# owl-digital-2.net
KiCad netlist of a schematic drawn in EAGLE
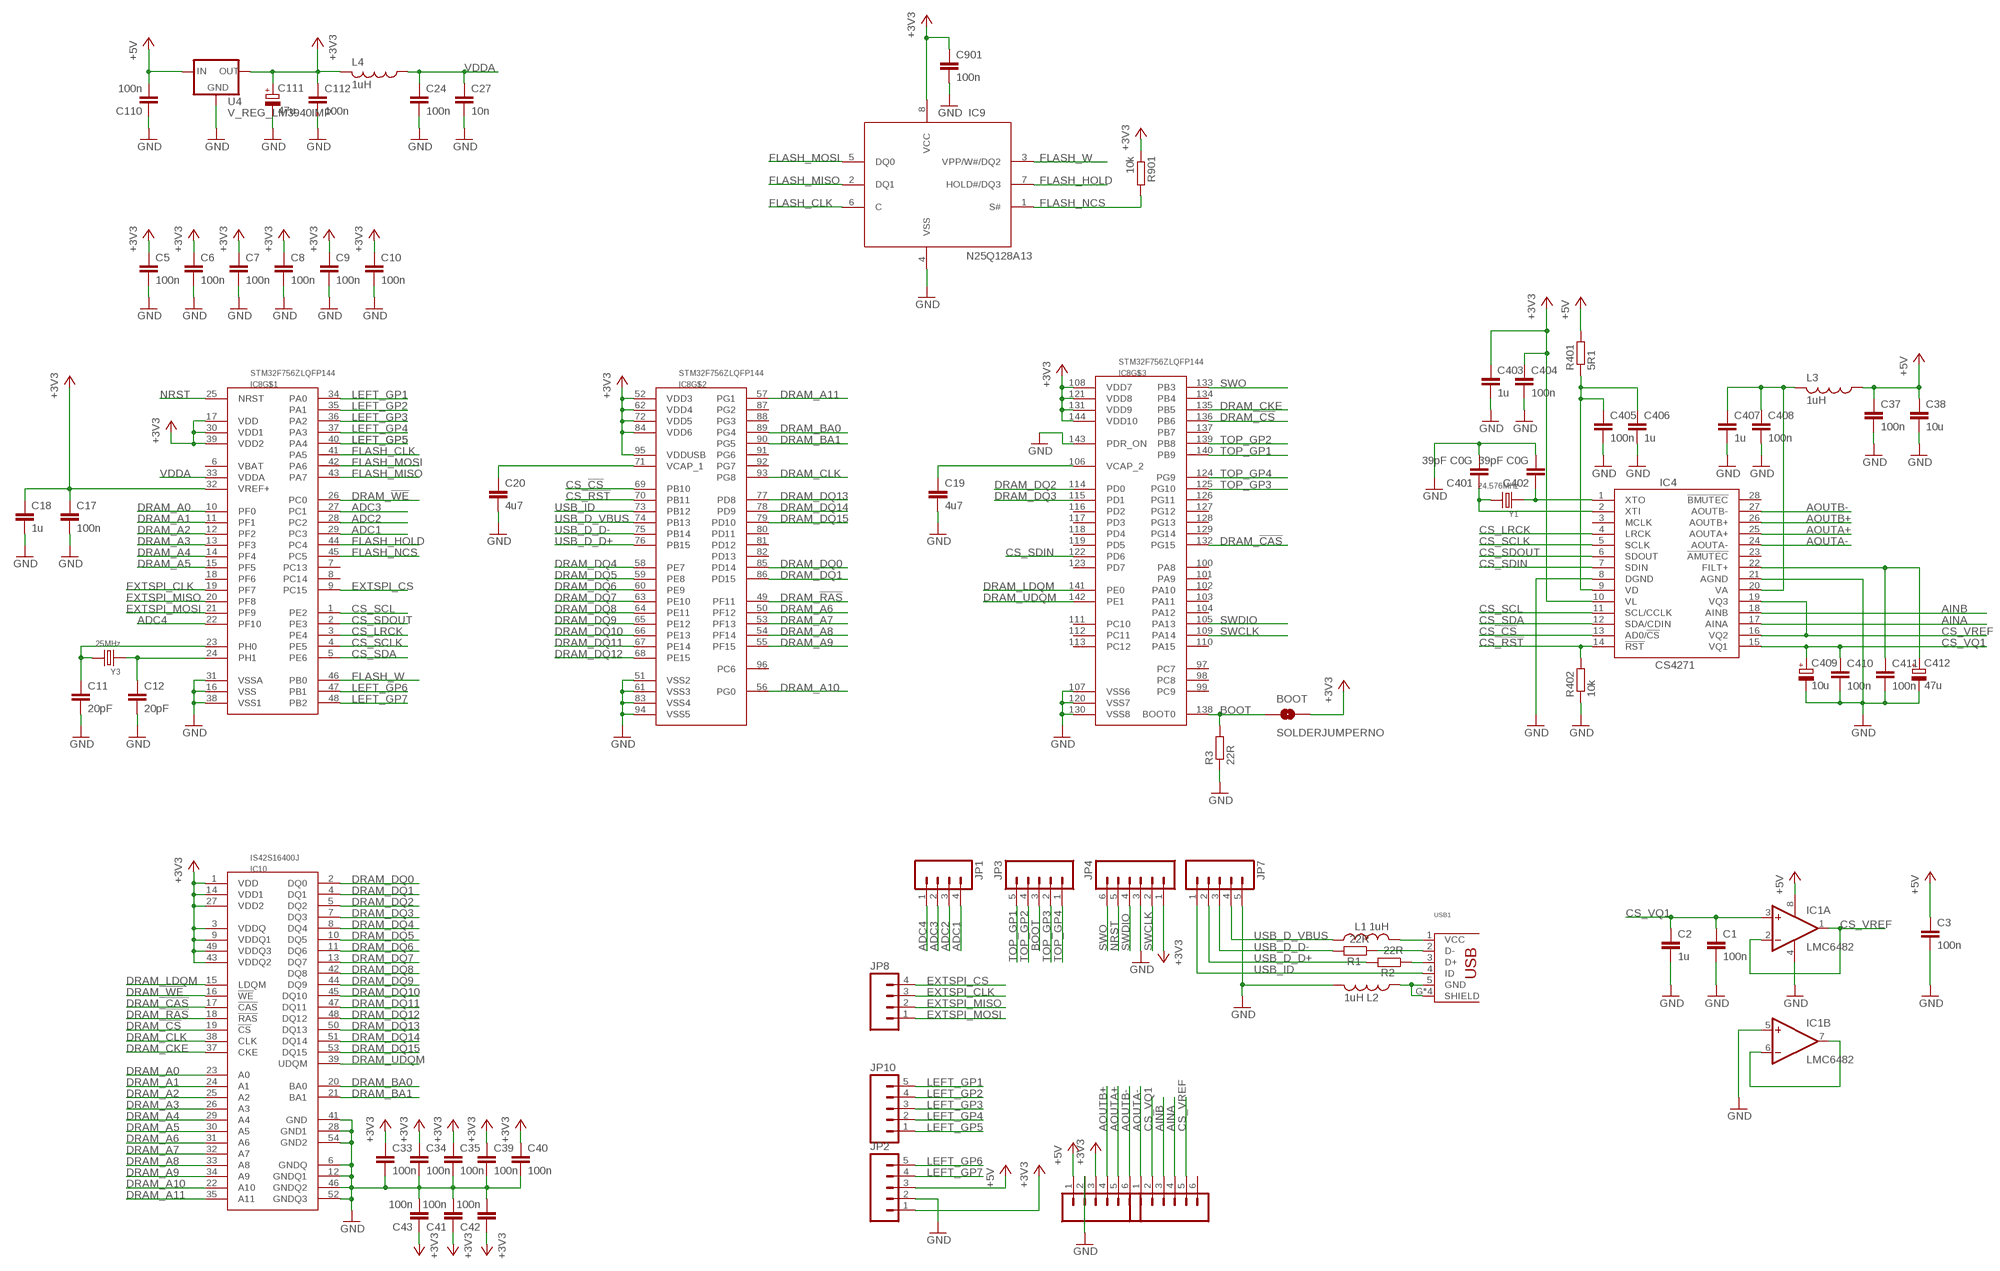
[diagram p0: schematic, sheet 1]

(export (version "E")
  (design (tool "Eeschema 10.0.6"))
  (components
    (comp (ref "BOOT")
      (value "SOLDERJUMPERNO")
      (footprint "eagle-import:SJ_2S-NO")
      (libsource (lib "eagle-import") (part "SOLDERJUMPERNO"))
    )
    (comp (ref "C1")
      (value "100n")
      (footprint "eagle-import:C0603")
      (libsource (lib "eagle-import") (part "C-EUC0603"))
    )
    (comp (ref "C2")
      (value "1u")
      (footprint "eagle-import:C0603")
      (libsource (lib "eagle-import") (part "C-EUC0603"))
    )
    (comp (ref "C3")
      (value "100n")
      (footprint "eagle-import:C0603")
      (libsource (lib "eagle-import") (part "C-EUC0603"))
    )
    (comp (ref "C5")
      (value "100n")
      (footprint "eagle-import:C0603")
      (libsource (lib "eagle-import") (part "C-EUC0603"))
    )
    (comp (ref "C6")
      (value "100n")
      (footprint "eagle-import:C0603")
      (libsource (lib "eagle-import") (part "C-EUC0603"))
    )
    (comp (ref "C7")
      (value "100n")
      (footprint "eagle-import:C0603")
      (libsource (lib "eagle-import") (part "C-EUC0603"))
    )
    (comp (ref "C8")
      (value "100n")
      (footprint "eagle-import:C0603")
      (libsource (lib "eagle-import") (part "C-EUC0603"))
    )
    (comp (ref "C9")
      (value "100n")
      (footprint "eagle-import:C0603")
      (libsource (lib "eagle-import") (part "C-EUC0603"))
    )
    (comp (ref "C10")
      (value "100n")
      (footprint "eagle-import:C0603")
      (libsource (lib "eagle-import") (part "C-EUC0603"))
    )
    (comp (ref "C11")
      (value "20pF")
      (footprint "eagle-import:C0603")
      (libsource (lib "eagle-import") (part "C-EUC0603"))
    )
    (comp (ref "C12")
      (value "20pF")
      (footprint "eagle-import:C0603")
      (libsource (lib "eagle-import") (part "C-EUC0603"))
    )
    (comp (ref "C17")
      (value "100n")
      (footprint "eagle-import:C0603")
      (libsource (lib "eagle-import") (part "C-EUC0603"))
    )
    (comp (ref "C18")
      (value "1u")
      (footprint "eagle-import:C0603")
      (libsource (lib "eagle-import") (part "C-EUC0603"))
    )
    (comp (ref "C19")
      (value "4u7")
      (footprint "eagle-import:C0603")
      (libsource (lib "eagle-import") (part "C-EUC0603"))
    )
    (comp (ref "C20")
      (value "4u7")
      (footprint "eagle-import:C0603")
      (libsource (lib "eagle-import") (part "C-EUC0603"))
    )
    (comp (ref "C24")
      (value "100n")
      (footprint "eagle-import:C0603")
      (libsource (lib "eagle-import") (part "C-EUC0603"))
    )
    (comp (ref "C27")
      (value "10n")
      (footprint "eagle-import:C0603")
      (libsource (lib "eagle-import") (part "C-EUC0603"))
    )
    (comp (ref "C33")
      (value "100n")
      (footprint "eagle-import:C0603")
      (libsource (lib "eagle-import") (part "C-EUC0603"))
    )
    (comp (ref "C34")
      (value "100n")
      (footprint "eagle-import:C0603")
      (libsource (lib "eagle-import") (part "C-EUC0603"))
    )
    (comp (ref "C35")
      (value "100n")
      (footprint "eagle-import:C0603")
      (libsource (lib "eagle-import") (part "C-EUC0603"))
    )
    (comp (ref "C37")
      (value "100n")
      (footprint "eagle-import:C0603")
      (libsource (lib "eagle-import") (part "C-EUC0603"))
    )
    (comp (ref "C38")
      (value "10u")
      (footprint "eagle-import:C1206")
      (libsource (lib "eagle-import") (part "C-EUC1206"))
    )
    (comp (ref "C39")
      (value "100n")
      (footprint "eagle-import:C0603")
      (libsource (lib "eagle-import") (part "C-EUC0603"))
    )
    (comp (ref "C40")
      (value "100n")
      (footprint "eagle-import:C0603")
      (libsource (lib "eagle-import") (part "C-EUC0603"))
    )
    (comp (ref "C41")
      (value "100n")
      (footprint "eagle-import:C0603")
      (libsource (lib "eagle-import") (part "C-EUC0603"))
    )
    (comp (ref "C42")
      (value "100n")
      (footprint "eagle-import:C0603")
      (libsource (lib "eagle-import") (part "C-EUC0603"))
    )
    (comp (ref "C43")
      (value "100n")
      (footprint "eagle-import:C0603")
      (libsource (lib "eagle-import") (part "C-EUC0603"))
    )
    (comp (ref "C110")
      (value "100n")
      (footprint "eagle-import:C0603")
      (libsource (lib "eagle-import") (part "C-EUC0603"))
    )
    (comp (ref "C111")
      (value "47u")
      (footprint "eagle-import:CPOL-5")
      (libsource (lib "eagle-import") (part "CPOL-EU153CLV-0505"))
    )
    (comp (ref "C112")
      (value "100n")
      (footprint "eagle-import:C0603")
      (libsource (lib "eagle-import") (part "C-EUC0603"))
    )
    (comp (ref "C401")
      (value "39pF C0G")
      (footprint "eagle-import:C0603")
      (libsource (lib "eagle-import") (part "C-EUC0603"))
    )
    (comp (ref "C402")
      (value "39pF C0G")
      (footprint "eagle-import:C0603")
      (libsource (lib "eagle-import") (part "C-EUC0603"))
    )
    (comp (ref "C403")
      (value "1u")
      (footprint "eagle-import:C0603")
      (libsource (lib "eagle-import") (part "C-EUC0603"))
    )
    (comp (ref "C404")
      (value "100n")
      (footprint "eagle-import:C0603")
      (libsource (lib "eagle-import") (part "C-EUC0603"))
    )
    (comp (ref "C405")
      (value "100n")
      (footprint "eagle-import:C0603")
      (libsource (lib "eagle-import") (part "C-EUC0603"))
    )
    (comp (ref "C406")
      (value "1u")
      (footprint "eagle-import:C0603")
      (libsource (lib "eagle-import") (part "C-EUC0603"))
    )
    (comp (ref "C407")
      (value "1u")
      (footprint "eagle-import:C0603")
      (libsource (lib "eagle-import") (part "C-EUC0603"))
    )
    (comp (ref "C408")
      (value "100n")
      (footprint "eagle-import:C0603")
      (libsource (lib "eagle-import") (part "C-EUC0603"))
    )
    (comp (ref "C409")
      (value "10u")
      (footprint "eagle-import:CPOL-5")
      (libsource (lib "eagle-import") (part "CPOL-EU153CLV-0505"))
    )
    (comp (ref "C410")
      (value "100n")
      (footprint "eagle-import:C0603")
      (libsource (lib "eagle-import") (part "C-EUC0603"))
    )
    (comp (ref "C411")
      (value "100n")
      (footprint "eagle-import:C0603")
      (libsource (lib "eagle-import") (part "C-EUC0603"))
    )
    (comp (ref "C412")
      (value "47u")
      (footprint "eagle-import:CPOL-5")
      (libsource (lib "eagle-import") (part "CPOL-EU153CLV-0505"))
    )
    (comp (ref "C901")
      (value "100n")
      (footprint "eagle-import:C0603")
      (libsource (lib "eagle-import") (part "C-EUC0603"))
    )
    (comp (ref "IC1")
      (value "LMC6482")
      (footprint "eagle-import:SO08")
      (libsource (lib "eagle-import") (part "1458DLM"))
    )
    (comp (ref "IC4")
      (value "CS4271")
      (footprint "eagle-import:TSSOP28-0.65-9.7X4.4MM")
      (libsource (lib "eagle-import") (part "CS4271"))
    )
    (comp (ref "IC8")
      (value "STM32F756ZLQFP144")
      (footprint "eagle-import:QFP50P2200X2200X160-144N")
      (fields (field (name "OC_FARNELL") "2484975"))
      (libsource (lib "eagle-import") (part "STM32F756ZLQFP144"))
    )
    (comp (ref "IC9")
      (value "N25Q128A13")
      (footprint "eagle-import:SO8W")
      (libsource (lib "eagle-import") (part "N25Q128A13"))
    )
    (comp (ref "IC10")
      (value "IS42S16400J")
      (footprint "eagle-import:TSOP54-400")
      (libsource (lib "eagle-import") (part "IS42S16400J"))
    )
    (comp (ref "JP1")
      (value "M04PTH")
      (footprint "eagle-import:1X04")
      (libsource (lib "eagle-import") (part "M04PTH"))
    )
    (comp (ref "JP2")
      (value "M05PTH")
      (footprint "eagle-import:1X05")
      (libsource (lib "eagle-import") (part "M05PTH"))
    )
    (comp (ref "JP3")
      (value "M05PTH")
      (footprint "eagle-import:1X05")
      (libsource (lib "eagle-import") (part "M05PTH"))
    )
    (comp (ref "JP4")
      (value "M06SIP")
      (footprint "eagle-import:1X06")
      (libsource (lib "eagle-import") (part "M06SIP"))
    )
    (comp (ref "JP5")
      (value "M06SIP")
      (footprint "eagle-import:1X06")
      (libsource (lib "eagle-import") (part "M06SIP"))
    )
    (comp (ref "JP6")
      (value "M06SIP")
      (footprint "eagle-import:1X06")
      (libsource (lib "eagle-import") (part "M06SIP"))
    )
    (comp (ref "JP7")
      (value "M05PTH")
      (footprint "eagle-import:1X05")
      (libsource (lib "eagle-import") (part "M05PTH"))
    )
    (comp (ref "JP8")
      (value "M04PTH")
      (footprint "eagle-import:1X04")
      (libsource (lib "eagle-import") (part "M04PTH"))
    )
    (comp (ref "JP10")
      (value "M05PTH")
      (footprint "eagle-import:1X05")
      (libsource (lib "eagle-import") (part "M05PTH"))
    )
    (comp (ref "L1")
      (value "1uH")
      (footprint "eagle-import:0603")
      (libsource (lib "eagle-import") (part "INDUCTOR"))
    )
    (comp (ref "L2")
      (value "1uH")
      (footprint "eagle-import:0603")
      (libsource (lib "eagle-import") (part "INDUCTOR"))
    )
    (comp (ref "L3")
      (value "1uH")
      (footprint "eagle-import:0603")
      (libsource (lib "eagle-import") (part "INDUCTOR"))
    )
    (comp (ref "L4")
      (value "1uH")
      (footprint "eagle-import:0603")
      (libsource (lib "eagle-import") (part "INDUCTOR"))
    )
    (comp (ref "R1")
      (value "22R")
      (footprint "eagle-import:0603")
      (libsource (lib "eagle-import") (part "R-EU_0603"))
    )
    (comp (ref "R2")
      (value "22R")
      (footprint "eagle-import:0603")
      (libsource (lib "eagle-import") (part "R-EU_0603"))
    )
    (comp (ref "R3")
      (value "22R")
      (footprint "eagle-import:0603")
      (libsource (lib "eagle-import") (part "R-EU_0603"))
    )
    (comp (ref "R401")
      (value "5R1")
      (footprint "eagle-import:0603")
      (libsource (lib "eagle-import") (part "R-EU_0603"))
    )
    (comp (ref "R402")
      (value "10k")
      (footprint "eagle-import:0603")
      (libsource (lib "eagle-import") (part "R-EU_0603"))
    )
    (comp (ref "R901")
      (value "10k")
      (footprint "eagle-import:0603")
      (libsource (lib "eagle-import") (part "R-EU_0603"))
    )
    (comp (ref "U4")
      (value "V_REG_LM3940IMP")
      (footprint "eagle-import:SOT223")
      (libsource (lib "eagle-import") (part "V_REG_LM3940IMP"))
    )
    (comp (ref "USB1")
      (value "USB_HRS_ZX62-B-5PA(11)MICRO.B")
      (footprint "eagle-import:HRS_ZX62RD-AB-5P8")
      (libsource (lib "eagle-import") (part "USB_HRS_ZX62-B-5PA(11)MICRO.B"))
    )
    (comp (ref "Y1")
      (value "24.576MHz")
      (footprint "eagle-import:X2-SMD-5.0X3.2X1.3MM")
      (fields (field (name "MPN") "5032/2P"))
      (libsource (lib "eagle-import") (part "SMD-CRYSTAL-8MHZ-20PF-20PPM(2P-5.0X3.2MM)"))
    )
    (comp (ref "Y3")
      (value "25MHz")
      (footprint "eagle-import:X2-SMD-5.0X3.2X1.3MM")
      (fields (field (name "MPN") "5032/2P"))
      (libsource (lib "eagle-import") (part "SMD-CRYSTAL-8MHZ-20PF-20PPM(2P-5.0X3.2MM)"))
    )
  )
  (nets
    (net (code "1") (name "+3V3") (class "Default")
      (node (ref "BOOT") (pin "2") (pinfunction "2_2") (pintype "passive"))
      (node (ref "C10") (pin "1") (pinfunction "1_1") (pintype "passive"))
      (node (ref "C111") (pin "+") (pinfunction "+_+") (pintype "passive"))
      (node (ref "C112") (pin "1") (pinfunction "1_1") (pintype "passive"))
      (node (ref "C17") (pin "1") (pinfunction "1_1") (pintype "passive"))
      (node (ref "C18") (pin "1") (pinfunction "1_1") (pintype "passive"))
      (node (ref "C33") (pin "1") (pinfunction "1_1") (pintype "passive"))
      (node (ref "C34") (pin "1") (pinfunction "1_1") (pintype "passive"))
      (node (ref "C35") (pin "1") (pinfunction "1_1") (pintype "passive"))
      (node (ref "C39") (pin "1") (pinfunction "1_1") (pintype "passive"))
      (node (ref "C40") (pin "1") (pinfunction "1_1") (pintype "passive"))
      (node (ref "C403") (pin "1") (pinfunction "1_1") (pintype "passive"))
      (node (ref "C404") (pin "1") (pinfunction "1_1") (pintype "passive"))
      (node (ref "C41") (pin "1") (pinfunction "1_1") (pintype "passive"))
      (node (ref "C42") (pin "1") (pinfunction "1_1") (pintype "passive"))
      (node (ref "C43") (pin "1") (pinfunction "1_1") (pintype "passive"))
      (node (ref "C5") (pin "1") (pinfunction "1_1") (pintype "passive"))
      (node (ref "C6") (pin "1") (pinfunction "1_1") (pintype "passive"))
      (node (ref "C7") (pin "1") (pinfunction "1_1") (pintype "passive"))
      (node (ref "C8") (pin "1") (pinfunction "1_1") (pintype "passive"))
      (node (ref "C9") (pin "1") (pinfunction "1_1") (pintype "passive"))
      (node (ref "C901") (pin "1") (pinfunction "1_1") (pintype "passive"))
      (node (ref "IC10") (pin "1") (pinfunction "VDD_1") (pintype "bidirectional"))
      (node (ref "IC10") (pin "14") (pinfunction "VDD1_14") (pintype "bidirectional"))
      (node (ref "IC10") (pin "27") (pinfunction "VDD2_27") (pintype "bidirectional"))
      (node (ref "IC10") (pin "3") (pinfunction "VDDQ_3") (pintype "bidirectional"))
      (node (ref "IC10") (pin "43") (pinfunction "VDDQ2_43") (pintype "bidirectional"))
      (node (ref "IC10") (pin "49") (pinfunction "VDDQ3_49") (pintype "bidirectional"))
      (node (ref "IC10") (pin "9") (pinfunction "VDDQ1_9") (pintype "bidirectional"))
      (node (ref "IC4") (pin "10") (pinfunction "VL_10") (pintype "bidirectional"))
      (node (ref "IC8") (pin "108") (pinfunction "VDD7_108") (pintype "bidirectional"))
      (node (ref "IC8") (pin "121") (pinfunction "VDD8_121") (pintype "bidirectional"))
      (node (ref "IC8") (pin "131") (pinfunction "VDD9_131") (pintype "bidirectional"))
      (node (ref "IC8") (pin "144") (pinfunction "VDD10_144") (pintype "bidirectional"))
      (node (ref "IC8") (pin "17") (pinfunction "VDD_17") (pintype "bidirectional"))
      (node (ref "IC8") (pin "30") (pinfunction "VDD1_30") (pintype "bidirectional"))
      (node (ref "IC8") (pin "32") (pinfunction "VREF+_32") (pintype "bidirectional"))
      (node (ref "IC8") (pin "39") (pinfunction "VDD2_39") (pintype "bidirectional"))
      (node (ref "IC8") (pin "52") (pinfunction "VDD3_52") (pintype "bidirectional"))
      (node (ref "IC8") (pin "62") (pinfunction "VDD4_62") (pintype "bidirectional"))
      (node (ref "IC8") (pin "72") (pinfunction "VDD5_72") (pintype "bidirectional"))
      (node (ref "IC8") (pin "84") (pinfunction "VDD6_84") (pintype "bidirectional"))
      (node (ref "IC8") (pin "95") (pinfunction "VDDUSB_95") (pintype "bidirectional"))
      (node (ref "IC9") (pin "8") (pinfunction "VCC_8") (pintype "bidirectional"))
      (node (ref "JP2") (pin "1") (pinfunction "1_1") (pintype "passive"))
      (node (ref "JP4") (pin "1") (pinfunction "1_1") (pintype "passive"))
      (node (ref "JP5") (pin "3") (pinfunction "3_3") (pintype "passive"))
      (node (ref "L4") (pin "2") (pinfunction "2_2") (pintype "passive"))
      (node (ref "R901") (pin "1") (pinfunction "1_1") (pintype "passive"))
      (node (ref "U4") (pin "3") (pinfunction "OUT_3") (pintype "output"))
    )
    (net (code "2") (name "+5V") (class "Default")
      (node (ref "C110") (pin "2") (pinfunction "2_2") (pintype "passive"))
      (node (ref "C3") (pin "1") (pinfunction "1_1") (pintype "passive"))
      (node (ref "C37") (pin "1") (pinfunction "1_1") (pintype "passive"))
      (node (ref "C38") (pin "1") (pinfunction "1_1") (pintype "passive"))
      (node (ref "IC1") (pin "8") (pinfunction "V+_8") (pintype "power_in"))
      (node (ref "JP2") (pin "3") (pinfunction "3_3") (pintype "passive"))
      (node (ref "JP5") (pin "1") (pinfunction "1_1") (pintype "passive"))
      (node (ref "L3") (pin "1") (pinfunction "1_1") (pintype "passive"))
      (node (ref "R401") (pin "2") (pinfunction "2_2") (pintype "passive"))
      (node (ref "U4") (pin "1") (pinfunction "IN_1") (pintype "input"))
    )
    (net (code "3") (name "/ADC1") (class "Default")
      (node (ref "IC8") (pin "29") (pinfunction "PC3_29") (pintype "bidirectional"))
      (node (ref "JP1") (pin "4") (pinfunction "4_4") (pintype "passive"))
    )
    (net (code "4") (name "/ADC2") (class "Default")
      (node (ref "IC8") (pin "28") (pinfunction "PC2_28") (pintype "bidirectional"))
      (node (ref "JP1") (pin "3") (pinfunction "3_3") (pintype "passive"))
    )
    (net (code "5") (name "/ADC3") (class "Default")
      (node (ref "IC8") (pin "27") (pinfunction "PC1_27") (pintype "bidirectional"))
      (node (ref "JP1") (pin "2") (pinfunction "2_2") (pintype "passive"))
    )
    (net (code "6") (name "/ADC4") (class "Default")
      (node (ref "IC8") (pin "22") (pinfunction "PF10_22") (pintype "bidirectional"))
      (node (ref "JP1") (pin "1") (pinfunction "1_1") (pintype "passive"))
    )
    (net (code "7") (name "/AINA") (class "Default")
      (node (ref "IC4") (pin "17") (pinfunction "AINA_17") (pintype "bidirectional"))
      (node (ref "JP6") (pin "4") (pinfunction "4_4") (pintype "passive"))
    )
    (net (code "8") (name "/AINB") (class "Default")
      (node (ref "IC4") (pin "18") (pinfunction "AINB_18") (pintype "bidirectional"))
      (node (ref "JP6") (pin "3") (pinfunction "3_3") (pintype "passive"))
    )
    (net (code "9") (name "/AOUTA+") (class "Default")
      (node (ref "IC4") (pin "25") (pinfunction "AOUTA+_25") (pintype "bidirectional"))
      (node (ref "JP5") (pin "5") (pinfunction "5_5") (pintype "passive"))
    )
    (net (code "10") (name "/AOUTA-") (class "Default")
      (node (ref "IC4") (pin "24") (pinfunction "AOUTA-_24") (pintype "bidirectional"))
      (node (ref "JP6") (pin "1") (pinfunction "1_1") (pintype "passive"))
    )
    (net (code "11") (name "/AOUTB+") (class "Default")
      (node (ref "IC4") (pin "26") (pinfunction "AOUTB+_26") (pintype "bidirectional"))
      (node (ref "JP5") (pin "4") (pinfunction "4_4") (pintype "passive"))
    )
    (net (code "12") (name "/AOUTB-") (class "Default")
      (node (ref "IC4") (pin "27") (pinfunction "AOUTB-_27") (pintype "bidirectional"))
      (node (ref "JP5") (pin "6") (pinfunction "6_6") (pintype "passive"))
    )
    (net (code "13") (name "/BOOT") (class "Default")
      (node (ref "BOOT") (pin "1") (pinfunction "1_1") (pintype "passive"))
      (node (ref "IC8") (pin "138") (pinfunction "BOOT0_138") (pintype "bidirectional"))
      (node (ref "JP3") (pin "3") (pinfunction "3_3") (pintype "passive"))
      (node (ref "R3") (pin "2") (pinfunction "2_2") (pintype "passive"))
    )
    (net (code "14") (name "/CS_LRCK") (class "Default")
      (node (ref "IC4") (pin "4") (pinfunction "LRCK_4") (pintype "bidirectional"))
      (node (ref "IC8") (pin "3") (pinfunction "PE4_3") (pintype "bidirectional"))
    )
    (net (code "15") (name "/CS_SCL") (class "Default")
      (node (ref "IC4") (pin "11") (pinfunction "SCL/CCLK_11") (pintype "bidirectional"))
      (node (ref "IC8") (pin "1") (pinfunction "PE2_1") (pintype "bidirectional"))
    )
    (net (code "16") (name "/CS_SCLK") (class "Default")
      (node (ref "IC4") (pin "5") (pinfunction "SCLK_5") (pintype "bidirectional"))
      (node (ref "IC8") (pin "4") (pinfunction "PE5_4") (pintype "bidirectional"))
    )
    (net (code "17") (name "/CS_SDA") (class "Default")
      (node (ref "IC4") (pin "12") (pinfunction "SDA/CDIN_12") (pintype "bidirectional"))
      (node (ref "IC8") (pin "5") (pinfunction "PE6_5") (pintype "bidirectional"))
    )
    (net (code "18") (name "/CS_SDIN") (class "Default")
      (node (ref "IC4") (pin "7") (pinfunction "SDIN_7") (pintype "bidirectional"))
      (node (ref "IC8") (pin "122") (pinfunction "PD6_122") (pintype "bidirectional"))
    )
    (net (code "19") (name "/CS_SDOUT") (class "Default")
      (node (ref "IC4") (pin "6") (pinfunction "SDOUT_6") (pintype "bidirectional"))
      (node (ref "IC8") (pin "2") (pinfunction "PE3_2") (pintype "bidirectional"))
    )
    (net (code "20") (name "/CS_VQ1") (class "Default")
      (node (ref "C1") (pin "1") (pinfunction "1_1") (pintype "passive"))
      (node (ref "C2") (pin "1") (pinfunction "1_1") (pintype "passive"))
      (node (ref "C409") (pin "+") (pinfunction "+_+") (pintype "passive"))
      (node (ref "C410") (pin "1") (pinfunction "1_1") (pintype "passive"))
      (node (ref "IC1") (pin "3") (pinfunction "+IN_3") (pintype "input"))
      (node (ref "IC4") (pin "15") (pinfunction "VQ1_15") (pintype "bidirectional"))
      (node (ref "JP6") (pin "2") (pinfunction "2_2") (pintype "passive"))
    )
    (net (code "21") (name "/CS_VREF") (class "Default")
      (node (ref "IC1") (pin "1") (pinfunction "OUT_1") (pintype "output"))
      (node (ref "IC1") (pin "2") (pinfunction "-IN_2") (pintype "input"))
      (node (ref "IC4") (pin "16") (pinfunction "VQ2_16") (pintype "bidirectional"))
      (node (ref "IC4") (pin "19") (pinfunction "VQ3_19") (pintype "bidirectional"))
      (node (ref "JP6") (pin "5") (pinfunction "5_5") (pintype "passive"))
    )
    (net (code "22") (name "/CS_~{CS}") (class "Default")
      (node (ref "IC4") (pin "13") (pinfunction "AD0/~{CS}_13") (pintype "bidirectional"))
      (node (ref "IC8") (pin "69") (pinfunction "PB10_69") (pintype "bidirectional"))
    )
    (net (code "23") (name "/CS_~{RST}") (class "Default")
      (node (ref "IC4") (pin "14") (pinfunction "~{RST}_14") (pintype "bidirectional"))
      (node (ref "IC8") (pin "70") (pinfunction "PB11_70") (pintype "bidirectional"))
      (node (ref "R402") (pin "2") (pinfunction "2_2") (pintype "passive"))
    )
    (net (code "24") (name "/DRAM_A0") (class "Default")
      (node (ref "IC10") (pin "23") (pinfunction "A0_23") (pintype "bidirectional"))
      (node (ref "IC8") (pin "10") (pinfunction "PF0_10") (pintype "bidirectional"))
    )
    (net (code "25") (name "/DRAM_A1") (class "Default")
      (node (ref "IC10") (pin "24") (pinfunction "A1_24") (pintype "bidirectional"))
      (node (ref "IC8") (pin "11") (pinfunction "PF1_11") (pintype "bidirectional"))
    )
    (net (code "26") (name "/DRAM_A2") (class "Default")
      (node (ref "IC10") (pin "25") (pinfunction "A2_25") (pintype "bidirectional"))
      (node (ref "IC8") (pin "12") (pinfunction "PF2_12") (pintype "bidirectional"))
    )
    (net (code "27") (name "/DRAM_A3") (class "Default")
      (node (ref "IC10") (pin "26") (pinfunction "A3_26") (pintype "bidirectional"))
      (node (ref "IC8") (pin "13") (pinfunction "PF3_13") (pintype "bidirectional"))
    )
    (net (code "28") (name "/DRAM_A4") (class "Default")
      (node (ref "IC10") (pin "29") (pinfunction "A4_29") (pintype "bidirectional"))
      (node (ref "IC8") (pin "14") (pinfunction "PF4_14") (pintype "bidirectional"))
    )
    (net (code "29") (name "/DRAM_A5") (class "Default")
      (node (ref "IC10") (pin "30") (pinfunction "A5_30") (pintype "bidirectional"))
      (node (ref "IC8") (pin "15") (pinfunction "PF5_15") (pintype "bidirectional"))
    )
    (net (code "30") (name "/DRAM_A6") (class "Default")
      (node (ref "IC10") (pin "31") (pinfunction "A6_31") (pintype "bidirectional"))
      (node (ref "IC8") (pin "50") (pinfunction "PF12_50") (pintype "bidirectional"))
    )
    (net (code "31") (name "/DRAM_A7") (class "Default")
      (node (ref "IC10") (pin "32") (pinfunction "A7_32") (pintype "bidirectional"))
      (node (ref "IC8") (pin "53") (pinfunction "PF13_53") (pintype "bidirectional"))
    )
    (net (code "32") (name "/DRAM_A8") (class "Default")
      (node (ref "IC10") (pin "33") (pinfunction "A8_33") (pintype "bidirectional"))
      (node (ref "IC8") (pin "54") (pinfunction "PF14_54") (pintype "bidirectional"))
    )
    (net (code "33") (name "/DRAM_A9") (class "Default")
      (node (ref "IC10") (pin "34") (pinfunction "A9_34") (pintype "bidirectional"))
      (node (ref "IC8") (pin "55") (pinfunction "PF15_55") (pintype "bidirectional"))
    )
    (net (code "34") (name "/DRAM_A10") (class "Default")
      (node (ref "IC10") (pin "22") (pinfunction "A10_22") (pintype "bidirectional"))
      (node (ref "IC8") (pin "56") (pinfunction "PG0_56") (pintype "bidirectional"))
    )
    (net (code "35") (name "/DRAM_A11") (class "Default")
      (node (ref "IC10") (pin "35") (pinfunction "A11_35") (pintype "bidirectional"))
      (node (ref "IC8") (pin "57") (pinfunction "PG1_57") (pintype "bidirectional"))
    )
    (net (code "36") (name "/DRAM_BA0") (class "Default")
      (node (ref "IC10") (pin "20") (pinfunction "BA0_20") (pintype "bidirectional"))
      (node (ref "IC8") (pin "89") (pinfunction "PG4_89") (pintype "bidirectional"))
    )
    (net (code "37") (name "/DRAM_BA1") (class "Default")
      (node (ref "IC10") (pin "21") (pinfunction "BA1_21") (pintype "bidirectional"))
      (node (ref "IC8") (pin "90") (pinfunction "PG5_90") (pintype "bidirectional"))
    )
    (net (code "38") (name "/DRAM_CKE") (class "Default")
      (node (ref "IC10") (pin "37") (pinfunction "CKE_37") (pintype "bidirectional"))
      (node (ref "IC8") (pin "135") (pinfunction "PB5_135") (pintype "bidirectional"))
    )
    (net (code "39") (name "/DRAM_CLK") (class "Default")
      (node (ref "IC10") (pin "38") (pinfunction "CLK_38") (pintype "bidirectional"))
      (node (ref "IC8") (pin "93") (pinfunction "PG8_93") (pintype "bidirectional"))
    )
    (net (code "40") (name "/DRAM_DQ0") (class "Default")
      (node (ref "IC10") (pin "2") (pinfunction "DQ0_2") (pintype "bidirectional"))
      (node (ref "IC8") (pin "85") (pinfunction "PD14_85") (pintype "bidirectional"))
    )
    (net (code "41") (name "/DRAM_DQ1") (class "Default")
      (node (ref "IC10") (pin "4") (pinfunction "DQ1_4") (pintype "bidirectional"))
      (node (ref "IC8") (pin "86") (pinfunction "PD15_86") (pintype "bidirectional"))
    )
    (net (code "42") (name "/DRAM_DQ2") (class "Default")
      (node (ref "IC10") (pin "5") (pinfunction "DQ2_5") (pintype "bidirectional"))
      (node (ref "IC8") (pin "114") (pinfunction "PD0_114") (pintype "bidirectional"))
    )
    (net (code "43") (name "/DRAM_DQ3") (class "Default")
      (node (ref "IC10") (pin "7") (pinfunction "DQ3_7") (pintype "bidirectional"))
      (node (ref "IC8") (pin "115") (pinfunction "PD1_115") (pintype "bidirectional"))
    )
    (net (code "44") (name "/DRAM_DQ4") (class "Default")
      (node (ref "IC10") (pin "8") (pinfunction "DQ4_8") (pintype "bidirectional"))
      (node (ref "IC8") (pin "58") (pinfunction "PE7_58") (pintype "bidirectional"))
    )
    (net (code "45") (name "/DRAM_DQ5") (class "Default")
      (node (ref "IC10") (pin "10") (pinfunction "DQ5_10") (pintype "bidirectional"))
      (node (ref "IC8") (pin "59") (pinfunction "PE8_59") (pintype "bidirectional"))
    )
    (net (code "46") (name "/DRAM_DQ6") (class "Default")
      (node (ref "IC10") (pin "11") (pinfunction "DQ6_11") (pintype "bidirectional"))
      (node (ref "IC8") (pin "60") (pinfunction "PE9_60") (pintype "bidirectional"))
    )
    (net (code "47") (name "/DRAM_DQ7") (class "Default")
      (node (ref "IC10") (pin "13") (pinfunction "DQ7_13") (pintype "bidirectional"))
      (node (ref "IC8") (pin "63") (pinfunction "PE10_63") (pintype "bidirectional"))
    )
    (net (code "48") (name "/DRAM_DQ8") (class "Default")
      (node (ref "IC10") (pin "42") (pinfunction "DQ8_42") (pintype "bidirectional"))
      (node (ref "IC8") (pin "64") (pinfunction "PE11_64") (pintype "bidirectional"))
    )
    (net (code "49") (name "/DRAM_DQ9") (class "Default")
      (node (ref "IC10") (pin "44") (pinfunction "DQ9_44") (pintype "bidirectional"))
      (node (ref "IC8") (pin "65") (pinfunction "PE12_65") (pintype "bidirectional"))
    )
    (net (code "50") (name "/DRAM_DQ10") (class "Default")
      (node (ref "IC10") (pin "45") (pinfunction "DQ10_45") (pintype "bidirectional"))
      (node (ref "IC8") (pin "66") (pinfunction "PE13_66") (pintype "bidirectional"))
    )
    (net (code "51") (name "/DRAM_DQ11") (class "Default")
      (node (ref "IC10") (pin "47") (pinfunction "DQ11_47") (pintype "bidirectional"))
      (node (ref "IC8") (pin "67") (pinfunction "PE14_67") (pintype "bidirectional"))
    )
    (net (code "52") (name "/DRAM_DQ12") (class "Default")
      (node (ref "IC10") (pin "48") (pinfunction "DQ12_48") (pintype "bidirectional"))
      (node (ref "IC8") (pin "68") (pinfunction "PE15_68") (pintype "bidirectional"))
    )
    (net (code "53") (name "/DRAM_DQ13") (class "Default")
      (node (ref "IC10") (pin "50") (pinfunction "DQ13_50") (pintype "bidirectional"))
      (node (ref "IC8") (pin "77") (pinfunction "PD8_77") (pintype "bidirectional"))
    )
    (net (code "54") (name "/DRAM_DQ14") (class "Default")
      (node (ref "IC10") (pin "51") (pinfunction "DQ14_51") (pintype "bidirectional"))
      (node (ref "IC8") (pin "78") (pinfunction "PD9_78") (pintype "bidirectional"))
    )
    (net (code "55") (name "/DRAM_DQ15") (class "Default")
      (node (ref "IC10") (pin "53") (pinfunction "DQ15_53") (pintype "bidirectional"))
      (node (ref "IC8") (pin "79") (pinfunction "PD10_79") (pintype "bidirectional"))
    )
    (net (code "56") (name "/DRAM_LDQM") (class "Default")
      (node (ref "IC10") (pin "15") (pinfunction "LDQM_15") (pintype "bidirectional"))
      (node (ref "IC8") (pin "141") (pinfunction "PE0_141") (pintype "bidirectional"))
    )
    (net (code "57") (name "/DRAM_UDQM") (class "Default")
      (node (ref "IC10") (pin "39") (pinfunction "UDQM_39") (pintype "bidirectional"))
      (node (ref "IC8") (pin "142") (pinfunction "PE1_142") (pintype "bidirectional"))
    )
    (net (code "58") (name "/DRAM_~{CAS}") (class "Default")
      (node (ref "IC10") (pin "17") (pinfunction "~{CAS}_17") (pintype "bidirectional"))
      (node (ref "IC8") (pin "132") (pinfunction "PG15_132") (pintype "bidirectional"))
    )
    (net (code "59") (name "/DRAM_~{CS}") (class "Default")
      (node (ref "IC10") (pin "19") (pinfunction "~{CS}_19") (pintype "bidirectional"))
      (node (ref "IC8") (pin "136") (pinfunction "PB6_136") (pintype "bidirectional"))
    )
    (net (code "60") (name "/DRAM_~{RAS}") (class "Default")
      (node (ref "IC10") (pin "18") (pinfunction "~{RAS}_18") (pintype "bidirectional"))
      (node (ref "IC8") (pin "49") (pinfunction "PF11_49") (pintype "bidirectional"))
    )
    (net (code "61") (name "/DRAM_~{WE}") (class "Default")
      (node (ref "IC10") (pin "16") (pinfunction "~{WE}_16") (pintype "bidirectional"))
      (node (ref "IC8") (pin "26") (pinfunction "PC0_26") (pintype "bidirectional"))
    )
    (net (code "62") (name "/EXTSPI_CLK") (class "Default")
      (node (ref "IC8") (pin "19") (pinfunction "PF7_19") (pintype "bidirectional"))
      (node (ref "JP8") (pin "3") (pinfunction "3_3") (pintype "passive"))
    )
    (net (code "63") (name "/EXTSPI_CS") (class "Default")
      (node (ref "IC8") (pin "9") (pinfunction "PC15_9") (pintype "bidirectional"))
      (node (ref "JP8") (pin "4") (pinfunction "4_4") (pintype "passive"))
    )
    (net (code "64") (name "/EXTSPI_MISO") (class "Default")
      (node (ref "IC8") (pin "20") (pinfunction "PF8_20") (pintype "bidirectional"))
      (node (ref "JP8") (pin "2") (pinfunction "2_2") (pintype "passive"))
    )
    (net (code "65") (name "/EXTSPI_MOSI") (class "Default")
      (node (ref "IC8") (pin "21") (pinfunction "PF9_21") (pintype "bidirectional"))
      (node (ref "JP8") (pin "1") (pinfunction "1_1") (pintype "passive"))
    )
    (net (code "66") (name "/FLASH_CLK") (class "Default")
      (node (ref "IC8") (pin "41") (pinfunction "PA5_41") (pintype "bidirectional"))
      (node (ref "IC9") (pin "6") (pinfunction "C_6") (pintype "bidirectional"))
    )
    (net (code "67") (name "/FLASH_HOLD") (class "Default")
      (node (ref "IC8") (pin "44") (pinfunction "PC4_44") (pintype "bidirectional"))
      (node (ref "IC9") (pin "7") (pinfunction "HOLD#/DQ3_7") (pintype "bidirectional"))
    )
    (net (code "68") (name "/FLASH_MISO") (class "Default")
      (node (ref "IC8") (pin "43") (pinfunction "PA7_43") (pintype "bidirectional"))
      (node (ref "IC9") (pin "2") (pinfunction "DQ1_2") (pintype "bidirectional"))
    )
    (net (code "69") (name "/FLASH_MOSI") (class "Default")
      (node (ref "IC8") (pin "42") (pinfunction "PA6_42") (pintype "bidirectional"))
      (node (ref "IC9") (pin "5") (pinfunction "DQ0_5") (pintype "bidirectional"))
    )
    (net (code "70") (name "/FLASH_NCS") (class "Default")
      (node (ref "IC8") (pin "45") (pinfunction "PC5_45") (pintype "bidirectional"))
      (node (ref "IC9") (pin "1") (pinfunction "S#_1") (pintype "bidirectional"))
      (node (ref "R901") (pin "2") (pinfunction "2_2") (pintype "passive"))
    )
    (net (code "71") (name "/FLASH_W") (class "Default")
      (node (ref "IC8") (pin "46") (pinfunction "PB0_46") (pintype "bidirectional"))
      (node (ref "IC9") (pin "3") (pinfunction "VPP/W#/DQ2_3") (pintype "bidirectional"))
    )
    (net (code "72") (name "/LEFT_GP1") (class "Default")
      (node (ref "IC8") (pin "34") (pinfunction "PA0_34") (pintype "bidirectional"))
      (node (ref "JP10") (pin "5") (pinfunction "5_5") (pintype "passive"))
    )
    (net (code "73") (name "/LEFT_GP2") (class "Default")
      (node (ref "IC8") (pin "35") (pinfunction "PA1_35") (pintype "bidirectional"))
      (node (ref "JP10") (pin "4") (pinfunction "4_4") (pintype "passive"))
    )
    (net (code "74") (name "/LEFT_GP3") (class "Default")
      (node (ref "IC8") (pin "36") (pinfunction "PA2_36") (pintype "bidirectional"))
      (node (ref "JP10") (pin "3") (pinfunction "3_3") (pintype "passive"))
    )
    (net (code "75") (name "/LEFT_GP4") (class "Default")
      (node (ref "IC8") (pin "37") (pinfunction "PA3_37") (pintype "bidirectional"))
      (node (ref "JP10") (pin "2") (pinfunction "2_2") (pintype "passive"))
    )
    (net (code "76") (name "/LEFT_GP5") (class "Default")
      (node (ref "IC8") (pin "40") (pinfunction "PA4_40") (pintype "bidirectional"))
      (node (ref "JP10") (pin "1") (pinfunction "1_1") (pintype "passive"))
    )
    (net (code "77") (name "/LEFT_GP6") (class "Default")
      (node (ref "IC8") (pin "47") (pinfunction "PB1_47") (pintype "bidirectional"))
      (node (ref "JP2") (pin "5") (pinfunction "5_5") (pintype "passive"))
    )
    (net (code "78") (name "/LEFT_GP7") (class "Default")
      (node (ref "IC8") (pin "48") (pinfunction "PB2_48") (pintype "bidirectional"))
      (node (ref "JP2") (pin "4") (pinfunction "4_4") (pintype "passive"))
    )
    (net (code "79") (name "/NRST") (class "Default")
      (node (ref "IC8") (pin "25") (pinfunction "NRST_25") (pintype "bidirectional"))
      (node (ref "JP4") (pin "5") (pinfunction "5_5") (pintype "passive"))
    )
    (net (code "80") (name "/SWCLK") (class "Default")
      (node (ref "IC8") (pin "109") (pinfunction "PA14_109") (pintype "bidirectional"))
      (node (ref "JP4") (pin "2") (pinfunction "2_2") (pintype "passive"))
    )
    (net (code "81") (name "/SWDIO") (class "Default")
      (node (ref "IC8") (pin "105") (pinfunction "PA13_105") (pintype "bidirectional"))
      (node (ref "JP4") (pin "4") (pinfunction "4_4") (pintype "passive"))
    )
    (net (code "82") (name "/SWO") (class "Default")
      (node (ref "IC8") (pin "133") (pinfunction "PB3_133") (pintype "bidirectional"))
      (node (ref "JP4") (pin "6") (pinfunction "6_6") (pintype "passive"))
    )
    (net (code "83") (name "/TOP_GP1") (class "Default")
      (node (ref "IC8") (pin "140") (pinfunction "PB9_140") (pintype "bidirectional"))
      (node (ref "JP3") (pin "5") (pinfunction "5_5") (pintype "passive"))
    )
    (net (code "84") (name "/TOP_GP2") (class "Default")
      (node (ref "IC8") (pin "139") (pinfunction "PB8_139") (pintype "bidirectional"))
      (node (ref "JP3") (pin "4") (pinfunction "4_4") (pintype "passive"))
    )
    (net (code "85") (name "/TOP_GP3") (class "Default")
      (node (ref "IC8") (pin "125") (pinfunction "PG10_125") (pintype "bidirectional"))
      (node (ref "JP3") (pin "2") (pinfunction "2_2") (pintype "passive"))
    )
    (net (code "86") (name "/TOP_GP4") (class "Default")
      (node (ref "IC8") (pin "124") (pinfunction "PG9_124") (pintype "bidirectional"))
      (node (ref "JP3") (pin "1") (pinfunction "1_1") (pintype "passive"))
    )
    (net (code "87") (name "/USB_D_D+") (class "Default")
      (node (ref "IC8") (pin "76") (pinfunction "PB15_76") (pintype "bidirectional"))
      (node (ref "JP7") (pin "2") (pinfunction "2_2") (pintype "passive"))
      (node (ref "R2") (pin "2") (pinfunction "2_2") (pintype "passive"))
    )
    (net (code "88") (name "/USB_D_D-") (class "Default")
      (node (ref "IC8") (pin "75") (pinfunction "PB14_75") (pintype "bidirectional"))
      (node (ref "JP7") (pin "3") (pinfunction "3_3") (pintype "passive"))
      (node (ref "R1") (pin "2") (pinfunction "2_2") (pintype "passive"))
    )
    (net (code "89") (name "/USB_D_VBUS") (class "Default")
      (node (ref "IC8") (pin "74") (pinfunction "PB13_74") (pintype "bidirectional"))
      (node (ref "JP7") (pin "4") (pinfunction "4_4") (pintype "passive"))
      (node (ref "L1") (pin "1") (pinfunction "1_1") (pintype "passive"))
    )
    (net (code "90") (name "/USB_ID") (class "Default")
      (node (ref "IC8") (pin "73") (pinfunction "PB12_73") (pintype "bidirectional"))
      (node (ref "JP7") (pin "1") (pinfunction "1_1") (pintype "passive"))
      (node (ref "USB1") (pin "4") (pinfunction "ID_4") (pintype "bidirectional"))
    )
    (net (code "91") (name "/VDDA") (class "Default")
      (node (ref "C24") (pin "1") (pinfunction "1_1") (pintype "passive"))
      (node (ref "C27") (pin "1") (pinfunction "1_1") (pintype "passive"))
      (node (ref "IC8") (pin "33") (pinfunction "VDDA_33") (pintype "bidirectional"))
      (node (ref "L4") (pin "1") (pinfunction "1_1") (pintype "passive"))
    )
    (net (code "92") (name "GND") (class "Default")
      (node (ref "C1") (pin "2") (pinfunction "2_2") (pintype "passive"))
      (node (ref "C10") (pin "2") (pinfunction "2_2") (pintype "passive"))
      (node (ref "C11") (pin "2") (pinfunction "2_2") (pintype "passive"))
      (node (ref "C110") (pin "1") (pinfunction "1_1") (pintype "passive"))
      (node (ref "C111") (pin "-") (pinfunction "-_-") (pintype "passive"))
      (node (ref "C112") (pin "2") (pinfunction "2_2") (pintype "passive"))
      (node (ref "C12") (pin "2") (pinfunction "2_2") (pintype "passive"))
      (node (ref "C17") (pin "2") (pinfunction "2_2") (pintype "passive"))
      (node (ref "C18") (pin "2") (pinfunction "2_2") (pintype "passive"))
      (node (ref "C19") (pin "2") (pinfunction "2_2") (pintype "passive"))
      (node (ref "C2") (pin "2") (pinfunction "2_2") (pintype "passive"))
      (node (ref "C20") (pin "2") (pinfunction "2_2") (pintype "passive"))
      (node (ref "C24") (pin "2") (pinfunction "2_2") (pintype "passive"))
      (node (ref "C27") (pin "2") (pinfunction "2_2") (pintype "passive"))
      (node (ref "C3") (pin "2") (pinfunction "2_2") (pintype "passive"))
      (node (ref "C33") (pin "2") (pinfunction "2_2") (pintype "passive"))
      (node (ref "C34") (pin "2") (pinfunction "2_2") (pintype "passive"))
      (node (ref "C35") (pin "2") (pinfunction "2_2") (pintype "passive"))
      (node (ref "C37") (pin "2") (pinfunction "2_2") (pintype "passive"))
      (node (ref "C38") (pin "2") (pinfunction "2_2") (pintype "passive"))
      (node (ref "C39") (pin "2") (pinfunction "2_2") (pintype "passive"))
      (node (ref "C40") (pin "2") (pinfunction "2_2") (pintype "passive"))
      (node (ref "C401") (pin "2") (pinfunction "2_2") (pintype "passive"))
      (node (ref "C402") (pin "2") (pinfunction "2_2") (pintype "passive"))
      (node (ref "C403") (pin "2") (pinfunction "2_2") (pintype "passive"))
      (node (ref "C404") (pin "2") (pinfunction "2_2") (pintype "passive"))
      (node (ref "C405") (pin "2") (pinfunction "2_2") (pintype "passive"))
      (node (ref "C406") (pin "2") (pinfunction "2_2") (pintype "passive"))
      (node (ref "C407") (pin "2") (pinfunction "2_2") (pintype "passive"))
      (node (ref "C408") (pin "2") (pinfunction "2_2") (pintype "passive"))
      (node (ref "C409") (pin "-") (pinfunction "-_-") (pintype "passive"))
      (node (ref "C41") (pin "2") (pinfunction "2_2") (pintype "passive"))
      (node (ref "C410") (pin "2") (pinfunction "2_2") (pintype "passive"))
      (node (ref "C411") (pin "2") (pinfunction "2_2") (pintype "passive"))
      (node (ref "C412") (pin "-") (pinfunction "-_-") (pintype "passive"))
      (node (ref "C42") (pin "2") (pinfunction "2_2") (pintype "passive"))
      (node (ref "C43") (pin "2") (pinfunction "2_2") (pintype "passive"))
      (node (ref "C5") (pin "2") (pinfunction "2_2") (pintype "passive"))
      (node (ref "C6") (pin "2") (pinfunction "2_2") (pintype "passive"))
      (node (ref "C7") (pin "2") (pinfunction "2_2") (pintype "passive"))
      (node (ref "C8") (pin "2") (pinfunction "2_2") (pintype "passive"))
      (node (ref "C9") (pin "2") (pinfunction "2_2") (pintype "passive"))
      (node (ref "C901") (pin "2") (pinfunction "2_2") (pintype "passive"))
      (node (ref "IC1") (pin "4") (pinfunction "V-_4") (pintype "power_in"))
      (node (ref "IC1") (pin "5") (pinfunction "+IN_5") (pintype "input"))
      (node (ref "IC10") (pin "12") (pinfunction "GNDQ1_12") (pintype "bidirectional"))
      (node (ref "IC10") (pin "28") (pinfunction "GND1_28") (pintype "bidirectional"))
      (node (ref "IC10") (pin "41") (pinfunction "GND_41") (pintype "bidirectional"))
      (node (ref "IC10") (pin "46") (pinfunction "GNDQ2_46") (pintype "bidirectional"))
      (node (ref "IC10") (pin "52") (pinfunction "GNDQ3_52") (pintype "bidirectional"))
      (node (ref "IC10") (pin "54") (pinfunction "GND2_54") (pintype "bidirectional"))
      (node (ref "IC10") (pin "6") (pinfunction "GNDQ_6") (pintype "bidirectional"))
      (node (ref "IC4") (pin "21") (pinfunction "AGND_21") (pintype "bidirectional"))
      (node (ref "IC4") (pin "8") (pinfunction "DGND_8") (pintype "bidirectional"))
      (node (ref "IC8") (pin "107") (pinfunction "VSS6_107") (pintype "bidirectional"))
      (node (ref "IC8") (pin "120") (pinfunction "VSS7_120") (pintype "bidirectional"))
      (node (ref "IC8") (pin "130") (pinfunction "VSS8_130") (pintype "bidirectional"))
      (node (ref "IC8") (pin "143") (pinfunction "PDR_ON_143") (pintype "bidirectional"))
      (node (ref "IC8") (pin "16") (pinfunction "VSS_16") (pintype "bidirectional"))
      (node (ref "IC8") (pin "31") (pinfunction "VSSA_31") (pintype "bidirectional"))
      (node (ref "IC8") (pin "38") (pinfunction "VSS1_38") (pintype "bidirectional"))
      (node (ref "IC8") (pin "51") (pinfunction "VSS2_51") (pintype "bidirectional"))
      (node (ref "IC8") (pin "61") (pinfunction "VSS3_61") (pintype "bidirectional"))
      (node (ref "IC8") (pin "83") (pinfunction "VSS4_83") (pintype "bidirectional"))
      (node (ref "IC8") (pin "94") (pinfunction "VSS5_94") (pintype "bidirectional"))
      (node (ref "IC9") (pin "4") (pinfunction "VSS_4") (pintype "bidirectional"))
      (node (ref "JP2") (pin "2") (pinfunction "2_2") (pintype "passive"))
      (node (ref "JP4") (pin "3") (pinfunction "3_3") (pintype "passive"))
      (node (ref "JP5") (pin "2") (pinfunction "2_2") (pintype "passive"))
      (node (ref "JP7") (pin "5") (pinfunction "5_5") (pintype "passive"))
      (node (ref "L2") (pin "2") (pinfunction "2_2") (pintype "passive"))
      (node (ref "R3") (pin "1") (pinfunction "1_1") (pintype "passive"))
      (node (ref "R402") (pin "1") (pinfunction "1_1") (pintype "passive"))
      (node (ref "U4") (pin "2") (pinfunction "GND_2") (pintype "input"))
    )
    (net (code "93") (name "Net-(IC1B--IN)") (class "Default")
      (node (ref "IC1") (pin "6") (pinfunction "-IN_6") (pintype "input"))
      (node (ref "IC1") (pin "7") (pinfunction "OUT_7") (pintype "output"))
    )
    (net (code "94") (name "Net-(IC4-FILT+)") (class "Default")
      (node (ref "C411") (pin "1") (pinfunction "1_1") (pintype "passive"))
      (node (ref "C412") (pin "+") (pinfunction "+_+") (pintype "passive"))
      (node (ref "IC4") (pin "22") (pinfunction "FILT+_22") (pintype "bidirectional"))
    )
    (net (code "95") (name "Net-(IC4-VA)") (class "Default")
      (node (ref "C407") (pin "1") (pinfunction "1_1") (pintype "passive"))
      (node (ref "C408") (pin "1") (pinfunction "1_1") (pintype "passive"))
      (node (ref "IC4") (pin "20") (pinfunction "VA_20") (pintype "bidirectional"))
      (node (ref "L3") (pin "2") (pinfunction "2_2") (pintype "passive"))
    )
    (net (code "96") (name "Net-(IC4-VD)") (class "Default")
      (node (ref "C405") (pin "1") (pinfunction "1_1") (pintype "passive"))
      (node (ref "C406") (pin "1") (pinfunction "1_1") (pintype "passive"))
      (node (ref "IC4") (pin "9") (pinfunction "VD_9") (pintype "bidirectional"))
      (node (ref "R401") (pin "1") (pinfunction "1_1") (pintype "passive"))
    )
    (net (code "97") (name "Net-(IC4-XTI)") (class "Default")
      (node (ref "C401") (pin "1") (pinfunction "1_1") (pintype "passive"))
      (node (ref "IC4") (pin "2") (pinfunction "XTI_2") (pintype "bidirectional"))
      (node (ref "Y1") (pin "2") (pinfunction "2_2") (pintype "passive"))
    )
    (net (code "98") (name "Net-(IC4-XTO)") (class "Default")
      (node (ref "C402") (pin "1") (pinfunction "1_1") (pintype "passive"))
      (node (ref "IC4") (pin "1") (pinfunction "XTO_1") (pintype "bidirectional"))
      (node (ref "Y1") (pin "1") (pinfunction "1_1") (pintype "passive"))
    )
    (net (code "99") (name "Net-(IC8A-PH0)") (class "Default")
      (node (ref "C11") (pin "1") (pinfunction "1_1") (pintype "passive"))
      (node (ref "IC8") (pin "23") (pinfunction "PH0_23") (pintype "bidirectional"))
      (node (ref "Y3") (pin "2") (pinfunction "2_2") (pintype "passive"))
    )
    (net (code "100") (name "Net-(IC8A-PH1)") (class "Default")
      (node (ref "C12") (pin "1") (pinfunction "1_1") (pintype "passive"))
      (node (ref "IC8") (pin "24") (pinfunction "PH1_24") (pintype "bidirectional"))
      (node (ref "Y3") (pin "1") (pinfunction "1_1") (pintype "passive"))
    )
    (net (code "101") (name "Net-(IC8B-VCAP_1)") (class "Default")
      (node (ref "C20") (pin "1") (pinfunction "1_1") (pintype "passive"))
      (node (ref "IC8") (pin "71") (pinfunction "VCAP_1_71") (pintype "bidirectional"))
    )
    (net (code "102") (name "Net-(IC8C-VCAP_2)") (class "Default")
      (node (ref "C19") (pin "1") (pinfunction "1_1") (pintype "passive"))
      (node (ref "IC8") (pin "106") (pinfunction "VCAP_2_106") (pintype "bidirectional"))
    )
    (net (code "103") (name "Net-(USB1-D+)") (class "Default")
      (node (ref "R2") (pin "1") (pinfunction "1_1") (pintype "passive"))
      (node (ref "USB1") (pin "3") (pinfunction "D+_3") (pintype "bidirectional"))
    )
    (net (code "104") (name "Net-(USB1-D-)") (class "Default")
      (node (ref "R1") (pin "1") (pinfunction "1_1") (pintype "passive"))
      (node (ref "USB1") (pin "2") (pinfunction "D-_2") (pintype "bidirectional"))
    )
    (net (code "105") (name "Net-(USB1-GND)") (class "Default")
      (node (ref "L2") (pin "1") (pinfunction "1_1") (pintype "passive"))
      (node (ref "USB1") (pin "5") (pinfunction "GND_5") (pintype "bidirectional"))
      (node (ref "USB1") (pin "G") (pinfunction "SHIELD_G") (pintype "bidirectional"))
      (node (ref "USB1") (pin "G2") (pinfunction "SHIELD_G2") (pintype "bidirectional"))
      (node (ref "USB1") (pin "G3") (pinfunction "SHIELD_G3") (pintype "bidirectional"))
      (node (ref "USB1") (pin "G4") (pinfunction "SHIELD_G4") (pintype "bidirectional"))
    )
    (net (code "106") (name "Net-(USB1-VCC)") (class "Default")
      (node (ref "L1") (pin "2") (pinfunction "2_2") (pintype "passive"))
      (node (ref "USB1") (pin "1") (pinfunction "VCC_1") (pintype "bidirectional"))
    )
    (net (code "107") (name "unconnected-(IC4-MCLK-Pad3)") (class "Default")
      (node (ref "IC4") (pin "3") (pinfunction "MCLK_3") (pintype "bidirectional"))
    )
    (net (code "108") (name "unconnected-(IC4-~{AMUTEC}-Pad23)") (class "Default")
      (node (ref "IC4") (pin "23") (pinfunction "~{AMUTEC}_23") (pintype "bidirectional"))
    )
    (net (code "109") (name "unconnected-(IC4-~{BMUTEC}-Pad28)") (class "Default")
      (node (ref "IC4") (pin "28") (pinfunction "~{BMUTEC}_28") (pintype "bidirectional"))
    )
    (net (code "110") (name "unconnected-(IC8A-PC13-Pad7)") (class "Default")
      (node (ref "IC8") (pin "7") (pinfunction "PC13_7") (pintype "bidirectional"))
    )
    (net (code "111") (name "unconnected-(IC8A-PC14-Pad8)") (class "Default")
      (node (ref "IC8") (pin "8") (pinfunction "PC14_8") (pintype "bidirectional"))
    )
    (net (code "112") (name "unconnected-(IC8A-PF6-Pad18)") (class "Default")
      (node (ref "IC8") (pin "18") (pinfunction "PF6_18") (pintype "bidirectional"))
    )
    (net (code "113") (name "unconnected-(IC8A-VBAT-Pad6)") (class "Default")
      (node (ref "IC8") (pin "6") (pinfunction "VBAT_6") (pintype "bidirectional"))
    )
    (net (code "114") (name "unconnected-(IC8B-PC6-Pad96)") (class "Default")
      (node (ref "IC8") (pin "96") (pinfunction "PC6_96") (pintype "bidirectional"))
    )
    (net (code "115") (name "unconnected-(IC8B-PD11-Pad80)") (class "Default")
      (node (ref "IC8") (pin "80") (pinfunction "PD11_80") (pintype "bidirectional"))
    )
    (net (code "116") (name "unconnected-(IC8B-PD12-Pad81)") (class "Default")
      (node (ref "IC8") (pin "81") (pinfunction "PD12_81") (pintype "bidirectional"))
    )
    (net (code "117") (name "unconnected-(IC8B-PD13-Pad82)") (class "Default")
      (node (ref "IC8") (pin "82") (pinfunction "PD13_82") (pintype "bidirectional"))
    )
    (net (code "118") (name "unconnected-(IC8B-PG2-Pad87)") (class "Default")
      (node (ref "IC8") (pin "87") (pinfunction "PG2_87") (pintype "bidirectional"))
    )
    (net (code "119") (name "unconnected-(IC8B-PG3-Pad88)") (class "Default")
      (node (ref "IC8") (pin "88") (pinfunction "PG3_88") (pintype "bidirectional"))
    )
    (net (code "120") (name "unconnected-(IC8B-PG6-Pad91)") (class "Default")
      (node (ref "IC8") (pin "91") (pinfunction "PG6_91") (pintype "bidirectional"))
    )
    (net (code "121") (name "unconnected-(IC8B-PG7-Pad92)") (class "Default")
      (node (ref "IC8") (pin "92") (pinfunction "PG7_92") (pintype "bidirectional"))
    )
    (net (code "122") (name "unconnected-(IC8C-PA8-Pad100)") (class "Default")
      (node (ref "IC8") (pin "100") (pinfunction "PA8_100") (pintype "bidirectional"))
    )
    (net (code "123") (name "unconnected-(IC8C-PA9-Pad101)") (class "Default")
      (node (ref "IC8") (pin "101") (pinfunction "PA9_101") (pintype "bidirectional"))
    )
    (net (code "124") (name "unconnected-(IC8C-PA10-Pad102)") (class "Default")
      (node (ref "IC8") (pin "102") (pinfunction "PA10_102") (pintype "bidirectional"))
    )
    (net (code "125") (name "unconnected-(IC8C-PA11-Pad103)") (class "Default")
      (node (ref "IC8") (pin "103") (pinfunction "PA11_103") (pintype "bidirectional"))
    )
    (net (code "126") (name "unconnected-(IC8C-PA12-Pad104)") (class "Default")
      (node (ref "IC8") (pin "104") (pinfunction "PA12_104") (pintype "bidirectional"))
    )
    (net (code "127") (name "unconnected-(IC8C-PA15-Pad110)") (class "Default")
      (node (ref "IC8") (pin "110") (pinfunction "PA15_110") (pintype "bidirectional"))
    )
    (net (code "128") (name "unconnected-(IC8C-PB4-Pad134)") (class "Default")
      (node (ref "IC8") (pin "134") (pinfunction "PB4_134") (pintype "bidirectional"))
    )
    (net (code "129") (name "unconnected-(IC8C-PB7-Pad137)") (class "Default")
      (node (ref "IC8") (pin "137") (pinfunction "PB7_137") (pintype "bidirectional"))
    )
    (net (code "130") (name "unconnected-(IC8C-PC7-Pad97)") (class "Default")
      (node (ref "IC8") (pin "97") (pinfunction "PC7_97") (pintype "bidirectional"))
    )
    (net (code "131") (name "unconnected-(IC8C-PC8-Pad98)") (class "Default")
      (node (ref "IC8") (pin "98") (pinfunction "PC8_98") (pintype "bidirectional"))
    )
    (net (code "132") (name "unconnected-(IC8C-PC9-Pad99)") (class "Default")
      (node (ref "IC8") (pin "99") (pinfunction "PC9_99") (pintype "bidirectional"))
    )
    (net (code "133") (name "unconnected-(IC8C-PC10-Pad111)") (class "Default")
      (node (ref "IC8") (pin "111") (pinfunction "PC10_111") (pintype "bidirectional"))
    )
    (net (code "134") (name "unconnected-(IC8C-PC11-Pad112)") (class "Default")
      (node (ref "IC8") (pin "112") (pinfunction "PC11_112") (pintype "bidirectional"))
    )
    (net (code "135") (name "unconnected-(IC8C-PC12-Pad113)") (class "Default")
      (node (ref "IC8") (pin "113") (pinfunction "PC12_113") (pintype "bidirectional"))
    )
    (net (code "136") (name "unconnected-(IC8C-PD2-Pad116)") (class "Default")
      (node (ref "IC8") (pin "116") (pinfunction "PD2_116") (pintype "bidirectional"))
    )
    (net (code "137") (name "unconnected-(IC8C-PD3-Pad117)") (class "Default")
      (node (ref "IC8") (pin "117") (pinfunction "PD3_117") (pintype "bidirectional"))
    )
    (net (code "138") (name "unconnected-(IC8C-PD4-Pad118)") (class "Default")
      (node (ref "IC8") (pin "118") (pinfunction "PD4_118") (pintype "bidirectional"))
    )
    (net (code "139") (name "unconnected-(IC8C-PD5-Pad119)") (class "Default")
      (node (ref "IC8") (pin "119") (pinfunction "PD5_119") (pintype "bidirectional"))
    )
    (net (code "140") (name "unconnected-(IC8C-PD7-Pad123)") (class "Default")
      (node (ref "IC8") (pin "123") (pinfunction "PD7_123") (pintype "bidirectional"))
    )
    (net (code "141") (name "unconnected-(IC8C-PG11-Pad126)") (class "Default")
      (node (ref "IC8") (pin "126") (pinfunction "PG11_126") (pintype "bidirectional"))
    )
    (net (code "142") (name "unconnected-(IC8C-PG12-Pad127)") (class "Default")
      (node (ref "IC8") (pin "127") (pinfunction "PG12_127") (pintype "bidirectional"))
    )
    (net (code "143") (name "unconnected-(IC8C-PG13-Pad128)") (class "Default")
      (node (ref "IC8") (pin "128") (pinfunction "PG13_128") (pintype "bidirectional"))
    )
    (net (code "144") (name "unconnected-(IC8C-PG14-Pad129)") (class "Default")
      (node (ref "IC8") (pin "129") (pinfunction "PG14_129") (pintype "bidirectional"))
    )
    (net (code "145") (name "unconnected-(JP6-Pad6)") (class "Default")
      (node (ref "JP6") (pin "6") (pinfunction "6_6") (pintype "passive"))
    )
  )
)
